# 09_PL_ETH_2.net
KiCad netlist of a schematic drawn in Altium Designer
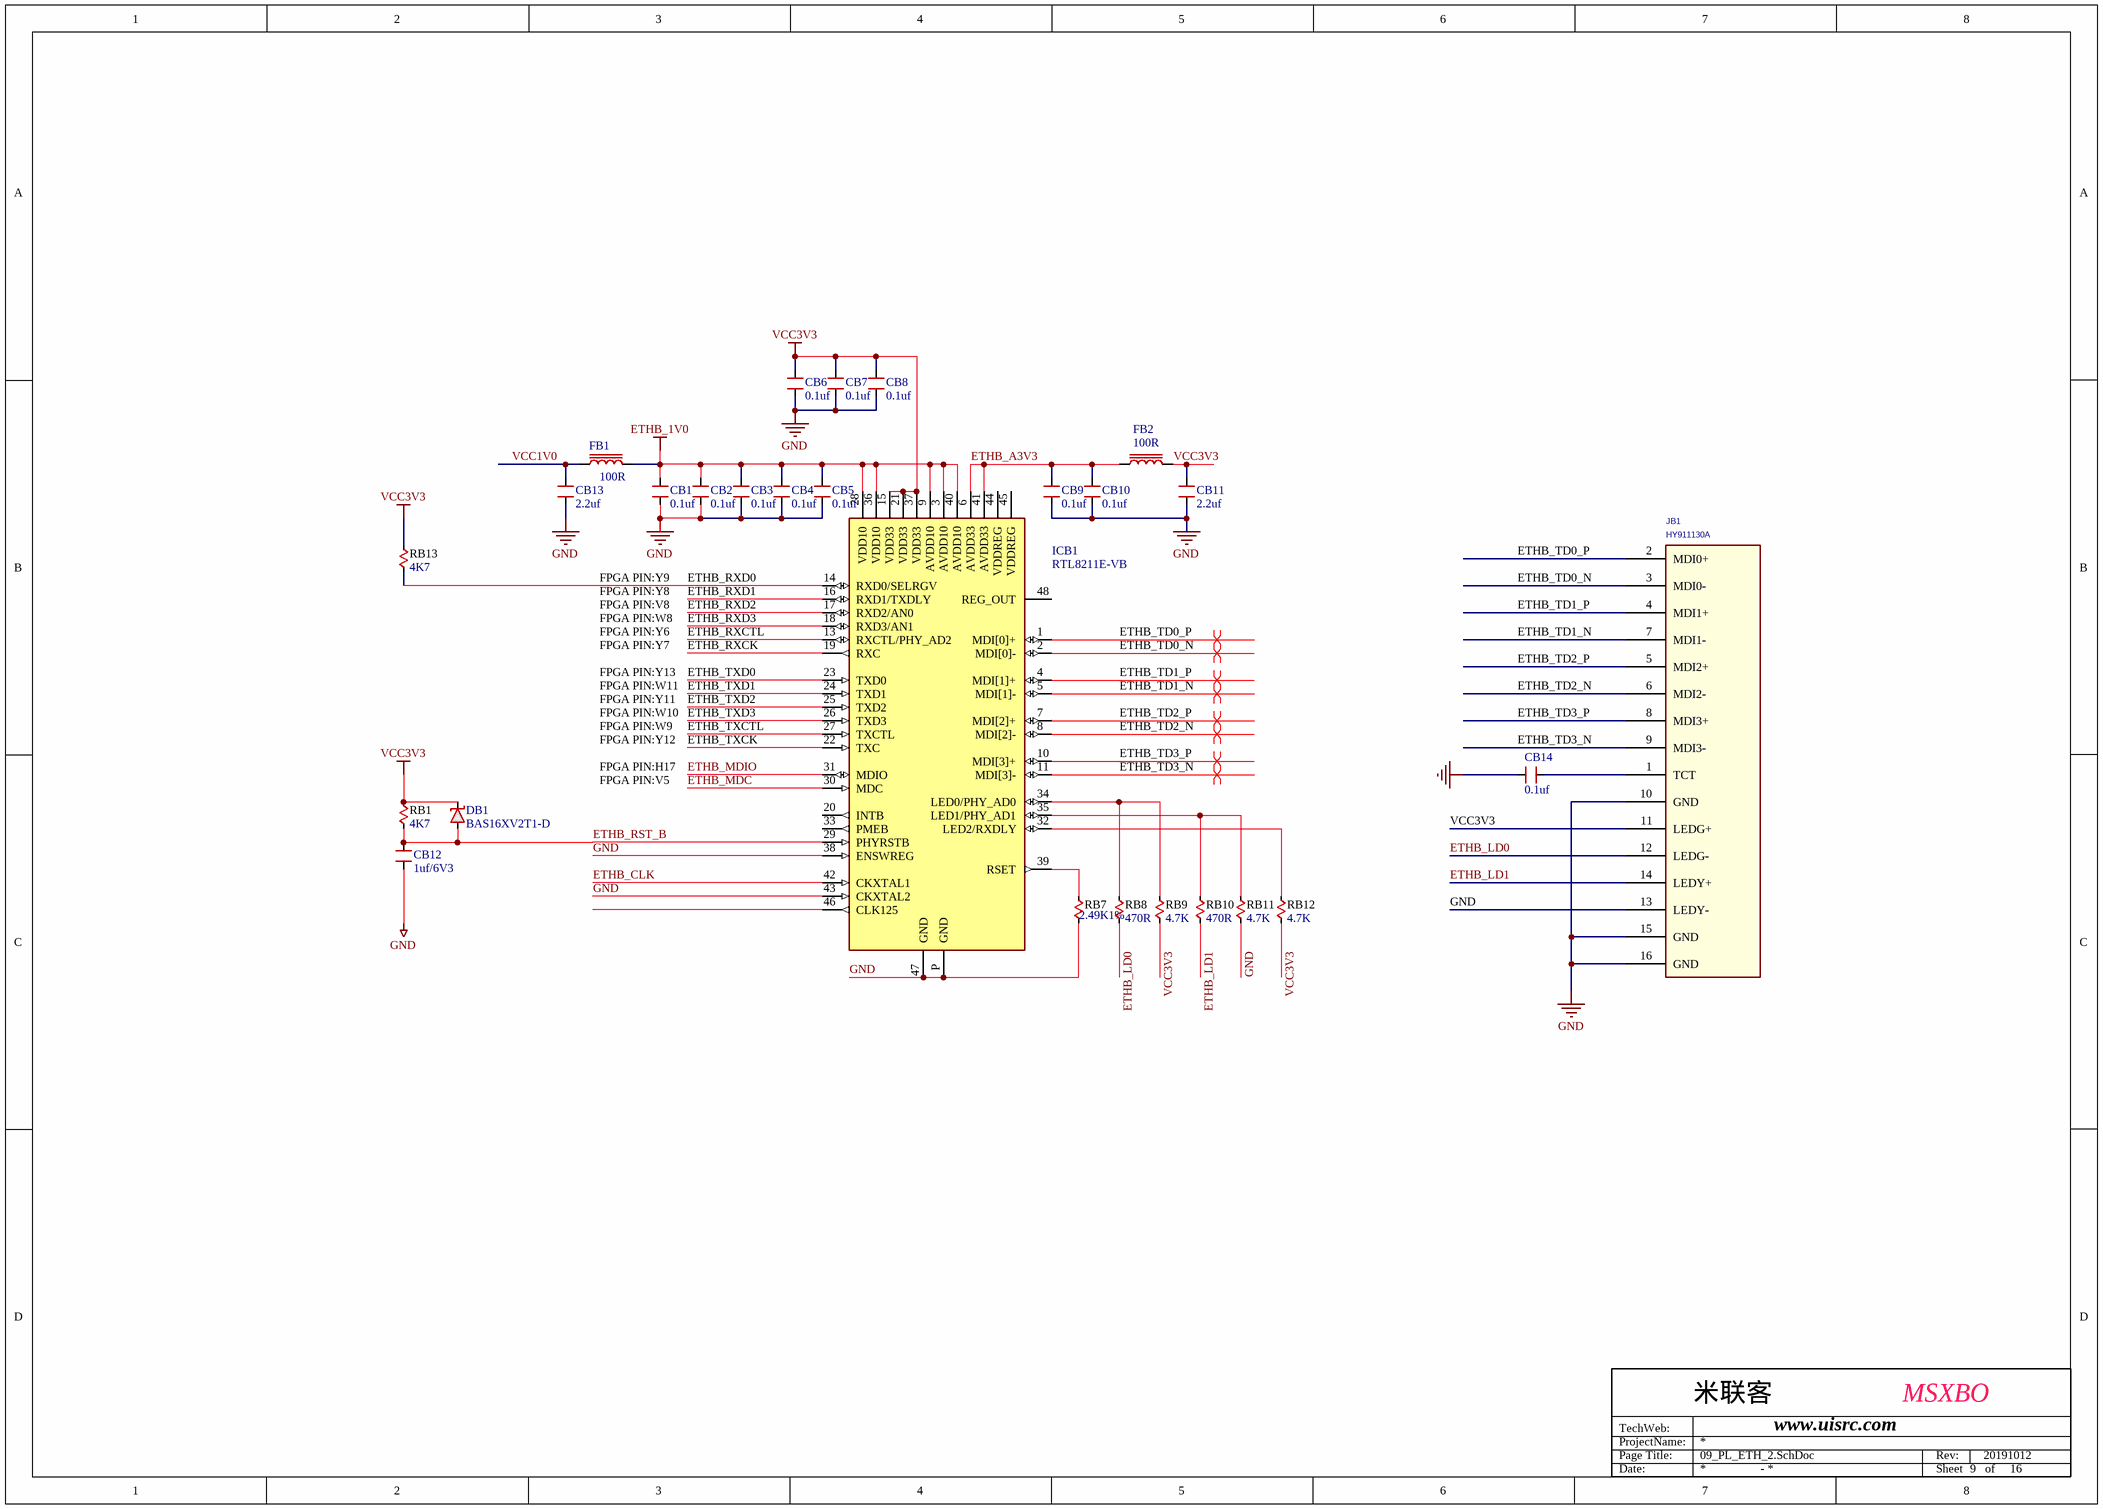
[diagram p0: 09_PL_ETH_2.SchDoc]

(export (version "E")
  (design (tool "Eeschema 10.0.6"))
  (components
    (comp (ref "CB1")
      (value "0.1uf")
      (footprint "CAP0402")
      (description "Generic Capacitor")
      (libsource (lib "Miz701_fun20160215") (part "CAPACITOR"))
    )
    (comp (ref "CB2")
      (value "0.1uf")
      (footprint "CAP0402")
      (description "Generic Capacitor")
      (libsource (lib "Miz701_fun20160215") (part "CAPACITOR"))
    )
    (comp (ref "CB3")
      (value "0.1uf")
      (footprint "CAP0402")
      (description "Generic Capacitor")
      (libsource (lib "Miz701_fun20160215") (part "CAPACITOR"))
    )
    (comp (ref "CB4")
      (value "0.1uf")
      (footprint "CAP0402")
      (description "Generic Capacitor")
      (libsource (lib "Miz701_fun20160215") (part "CAPACITOR"))
    )
    (comp (ref "CB5")
      (value "0.1uf")
      (footprint "CAP0402")
      (description "Generic Capacitor")
      (libsource (lib "Miz701_fun20160215") (part "CAPACITOR"))
    )
    (comp (ref "CB6")
      (value "0.1uf")
      (footprint "CAP0402")
      (description "Generic Capacitor")
      (libsource (lib "Miz701_fun20160215") (part "CAPACITOR"))
    )
    (comp (ref "CB7")
      (value "0.1uf")
      (footprint "CAP0402")
      (description "Generic Capacitor")
      (libsource (lib "Miz701_fun20160215") (part "CAPACITOR"))
    )
    (comp (ref "CB8")
      (value "0.1uf")
      (footprint "CAP0402")
      (description "Generic Capacitor")
      (libsource (lib "Miz701_fun20160215") (part "CAPACITOR"))
    )
    (comp (ref "CB9")
      (value "0.1uf")
      (footprint "CAP0402")
      (description "Generic Capacitor")
      (libsource (lib "Miz701_fun20160215") (part "CAPACITOR"))
    )
    (comp (ref "CB10")
      (value "0.1uf")
      (footprint "CAP0402")
      (description "Generic Capacitor")
      (libsource (lib "Miz701_fun20160215") (part "CAPACITOR"))
    )
    (comp (ref "CB11")
      (value "2.2uf")
      (footprint "CAP0402")
      (description "Generic Capacitor")
      (libsource (lib "Miz701_fun20160215") (part "CAPACITOR"))
    )
    (comp (ref "CB12")
      (value "1uf/6V3")
      (footprint "CAP0402")
      (description "Generic Capacitor")
      (fields (field (name "MANUFACTURER") "Murata"))
      (libsource (lib "Miz702N_fun") (part "CAPACITOR"))
    )
    (comp (ref "CB13")
      (value "2.2uf")
      (footprint "CAP0402")
      (description "Generic Capacitor")
      (libsource (lib "Miz701_fun20160215") (part "CAPACITOR"))
    )
    (comp (ref "CB14")
      (value "0.1uf")
      (footprint "CAP0402")
      (description "Generic Capacitor")
      (libsource (lib "Miz701_fun20160215") (part "CAPACITOR"))
    )
    (comp (ref "DB1")
      (value "BAS16XV2T1-D")
      (footprint "SOD-523")
      (description "Surface Mount ESD Protection Diode")
      (fields (field (name "MANUFACTURER") "On Semiconductor"))
      (libsource (lib "Miz702N_fun") (part "DIODE-SCH"))
    )
    (comp (ref "FB1")
      (value "100R")
      (footprint "CAP0603")
      (description "Generic Ferrite Bead")
      (libsource (lib "Digilent") (part "Ferrite Bead"))
    )
    (comp (ref "FB2")
      (value "100R")
      (footprint "CAP0603")
      (description "Generic Ferrite Bead")
      (libsource (lib "Digilent") (part "Ferrite Bead"))
    )
    (comp (ref "ICB1")
      (value "RTL8211E-VB")
      (footprint "QFN48")
      (libsource (lib "Miz701_fun20160215") (part "RTL8211E-VL"))
    )
    (comp (ref "JB1") (value "HY911130A") (footprint "HY911130A") (libsource (lib "*") (part "HY911130A")))
    (comp (ref "RB1")
      (value "4K7")
      (footprint "RES0402")
      (description "Generic Resistor")
      (libsource (lib "Miz702N_fun") (part "RESISTOR"))
    )
    (comp (ref "RB7")
      (value "2.49K1%")
      (footprint "RES0402")
      (description "Generic Resistor")
      (libsource (lib "Miz701_fun20160215") (part "RESISTOR"))
    )
    (comp (ref "RB8")
      (value "470R")
      (footprint "RES0402")
      (description "Generic Resistor")
      (libsource (lib "Miz701_fun20160215") (part "RESISTOR"))
    )
    (comp (ref "RB9")
      (value "4.7K")
      (footprint "RES0402")
      (description "Generic Resistor")
      (libsource (lib "Miz701_fun20160215") (part "RESISTOR"))
    )
    (comp (ref "RB10")
      (value "470R")
      (footprint "RES0402")
      (description "Generic Resistor")
      (libsource (lib "Miz701_fun20160215") (part "RESISTOR"))
    )
    (comp (ref "RB11")
      (value "4.7K")
      (footprint "RES0402")
      (description "Generic Resistor")
      (libsource (lib "Miz701_fun20160215") (part "RESISTOR"))
    )
    (comp (ref "RB12")
      (value "4.7K")
      (footprint "RES0402")
      (description "Generic Resistor")
      (libsource (lib "Miz701_fun20160215") (part "RESISTOR"))
    )
    (comp (ref "RB13")
      (value "4K7")
      (footprint "RES0402")
      (description "Generic Resistor")
      (libsource (lib "Miz702N_fun") (part "RESISTOR"))
    )
  )
  (nets
    (net (code "1") (name "/ETHB_A3V3") (class "Default")
      (node (ref "CB10") (pin "1") (pinfunction "1_1") (pintype "passive"))
      (node (ref "CB9") (pin "1") (pinfunction "1_1") (pintype "passive"))
      (node (ref "FB2") (pin "1") (pinfunction "1_1") (pintype "passive"))
      (node (ref "ICB1") (pin "41") (pinfunction "AVDD33_41") (pintype "power_in"))
      (node (ref "ICB1") (pin "6") (pinfunction "AVDD33_6") (pintype "power_in"))
    )
    (net (code "2") (name "/ETHB_CLK") (class "Default")
      (node (ref "ICB1") (pin "42") (pinfunction "CKXTAL1_42") (pintype "input"))
    )
    (net (code "3") (name "/ETHB_LD0") (class "Default")
      (node (ref "JB1") (pin "12") (pinfunction "LEDG-_12") (pintype "passive"))
      (node (ref "RB8") (pin "2") (pinfunction "2_2") (pintype "passive"))
    )
    (net (code "4") (name "/ETHB_LD1") (class "Default")
      (node (ref "JB1") (pin "14") (pinfunction "LEDY+_14") (pintype "passive"))
      (node (ref "RB10") (pin "2") (pinfunction "2_2") (pintype "passive"))
    )
    (net (code "5") (name "/ETHB_MDC") (class "Default")
      (node (ref "ICB1") (pin "30") (pinfunction "MDC_30") (pintype "input"))
    )
    (net (code "6") (name "/ETHB_MDIO") (class "Default")
      (node (ref "ICB1") (pin "31") (pinfunction "MDIO_31") (pintype "bidirectional"))
    )
    (net (code "7") (name "/ETHB_RST_B") (class "Default")
      (node (ref "CB12") (pin "1") (pinfunction "1_1") (pintype "passive"))
      (node (ref "DB1") (pin "A") (pinfunction "A_A") (pintype "passive"))
      (node (ref "ICB1") (pin "29") (pinfunction "PHYRSTB_29") (pintype "input"))
      (node (ref "RB1") (pin "2") (pinfunction "2_2") (pintype "passive"))
    )
    (net (code "8") (name "/ETHB_RXCK") (class "Default")
      (node (ref "ICB1") (pin "19") (pinfunction "RXC_19") (pintype "output"))
    )
    (net (code "9") (name "/ETHB_RXCTL") (class "Default")
      (node (ref "ICB1") (pin "13") (pinfunction "RXCTL/PHY_AD2_13") (pintype "bidirectional"))
    )
    (net (code "10") (name "/ETHB_RXD0") (class "Default")
      (node (ref "ICB1") (pin "14") (pinfunction "RXD0/SELRGV_14") (pintype "bidirectional"))
      (node (ref "RB13") (pin "2") (pinfunction "2_2") (pintype "passive"))
    )
    (net (code "11") (name "/ETHB_RXD1") (class "Default")
      (node (ref "ICB1") (pin "16") (pinfunction "RXD1/TXDLY_16") (pintype "bidirectional"))
    )
    (net (code "12") (name "/ETHB_RXD2") (class "Default")
      (node (ref "ICB1") (pin "17") (pinfunction "RXD2/AN0_17") (pintype "bidirectional"))
    )
    (net (code "13") (name "/ETHB_RXD3") (class "Default")
      (node (ref "ICB1") (pin "18") (pinfunction "RXD3/AN1_18") (pintype "bidirectional"))
    )
    (net (code "14") (name "/ETHB_TD0_N") (class "Default")
      (node (ref "ICB1") (pin "2") (pinfunction "MDI[0]-_2") (pintype "bidirectional"))
      (node (ref "JB1") (pin "3") (pinfunction "MDI0-_3") (pintype "passive"))
    )
    (net (code "15") (name "/ETHB_TD0_P") (class "Default")
      (node (ref "ICB1") (pin "1") (pinfunction "MDI[0]+_1") (pintype "bidirectional"))
      (node (ref "JB1") (pin "2") (pinfunction "MDI0+_2") (pintype "passive"))
    )
    (net (code "16") (name "/ETHB_TD1_N") (class "Default")
      (node (ref "ICB1") (pin "5") (pinfunction "MDI[1]-_5") (pintype "bidirectional"))
      (node (ref "JB1") (pin "7") (pinfunction "MDI1-_7") (pintype "passive"))
    )
    (net (code "17") (name "/ETHB_TD1_P") (class "Default")
      (node (ref "ICB1") (pin "4") (pinfunction "MDI[1]+_4") (pintype "bidirectional"))
      (node (ref "JB1") (pin "4") (pinfunction "MDI1+_4") (pintype "passive"))
    )
    (net (code "18") (name "/ETHB_TD2_N") (class "Default")
      (node (ref "ICB1") (pin "8") (pinfunction "MDI[2]-_8") (pintype "bidirectional"))
      (node (ref "JB1") (pin "6") (pinfunction "MDI2-_6") (pintype "passive"))
    )
    (net (code "19") (name "/ETHB_TD2_P") (class "Default")
      (node (ref "ICB1") (pin "7") (pinfunction "MDI[2]+_7") (pintype "bidirectional"))
      (node (ref "JB1") (pin "5") (pinfunction "MDI2+_5") (pintype "passive"))
    )
    (net (code "20") (name "/ETHB_TD3_N") (class "Default")
      (node (ref "ICB1") (pin "11") (pinfunction "MDI[3]-_11") (pintype "bidirectional"))
      (node (ref "JB1") (pin "9") (pinfunction "MDI3-_9") (pintype "passive"))
    )
    (net (code "21") (name "/ETHB_TD3_P") (class "Default")
      (node (ref "ICB1") (pin "10") (pinfunction "MDI[3]+_10") (pintype "bidirectional"))
      (node (ref "JB1") (pin "8") (pinfunction "MDI3+_8") (pintype "passive"))
    )
    (net (code "22") (name "/ETHB_TXCK") (class "Default")
      (node (ref "ICB1") (pin "22") (pinfunction "TXC_22") (pintype "input"))
    )
    (net (code "23") (name "/ETHB_TXCTL") (class "Default")
      (node (ref "ICB1") (pin "27") (pinfunction "TXCTL_27") (pintype "input"))
    )
    (net (code "24") (name "/ETHB_TXD0") (class "Default")
      (node (ref "ICB1") (pin "23") (pinfunction "TXD0_23") (pintype "input"))
    )
    (net (code "25") (name "/ETHB_TXD1") (class "Default")
      (node (ref "ICB1") (pin "24") (pinfunction "TXD1_24") (pintype "input"))
    )
    (net (code "26") (name "/ETHB_TXD2") (class "Default")
      (node (ref "ICB1") (pin "25") (pinfunction "TXD2_25") (pintype "input"))
    )
    (net (code "27") (name "/ETHB_TXD3") (class "Default")
      (node (ref "ICB1") (pin "26") (pinfunction "TXD3_26") (pintype "input"))
    )
    (net (code "28") (name "/VCC1V0") (class "Default")
      (node (ref "CB13") (pin "1") (pinfunction "1_1") (pintype "passive"))
      (node (ref "FB1") (pin "1") (pinfunction "1_1") (pintype "passive"))
    )
    (net (code "29") (name "ETHB_1V0") (class "Default")
      (node (ref "CB1") (pin "1") (pinfunction "1_1") (pintype "passive"))
      (node (ref "CB2") (pin "1") (pinfunction "1_1") (pintype "passive"))
      (node (ref "CB3") (pin "1") (pinfunction "1_1") (pintype "passive"))
      (node (ref "CB4") (pin "1") (pinfunction "1_1") (pintype "passive"))
      (node (ref "CB5") (pin "1") (pinfunction "1_1") (pintype "passive"))
      (node (ref "FB1") (pin "2") (pinfunction "2_2") (pintype "passive"))
      (node (ref "ICB1") (pin "28") (pinfunction "VDD10_28") (pintype "power_in"))
      (node (ref "ICB1") (pin "3") (pinfunction "AVDD10_3") (pintype "power_in"))
      (node (ref "ICB1") (pin "36") (pinfunction "VDD10_36") (pintype "power_in"))
      (node (ref "ICB1") (pin "40") (pinfunction "AVDD10_40") (pintype "power_in"))
      (node (ref "ICB1") (pin "9") (pinfunction "AVDD10_9") (pintype "power_in"))
    )
    (net (code "30") (name "GND") (class "Default")
      (node (ref "CB1") (pin "2") (pinfunction "2_2") (pintype "passive"))
      (node (ref "CB10") (pin "2") (pinfunction "2_2") (pintype "passive"))
      (node (ref "CB11") (pin "2") (pinfunction "2_2") (pintype "passive"))
      (node (ref "CB12") (pin "2") (pinfunction "2_2") (pintype "passive"))
      (node (ref "CB13") (pin "2") (pinfunction "2_2") (pintype "passive"))
      (node (ref "CB14") (pin "1") (pinfunction "1_1") (pintype "passive"))
      (node (ref "CB2") (pin "2") (pinfunction "2_2") (pintype "passive"))
      (node (ref "CB3") (pin "2") (pinfunction "2_2") (pintype "passive"))
      (node (ref "CB4") (pin "2") (pinfunction "2_2") (pintype "passive"))
      (node (ref "CB5") (pin "2") (pinfunction "2_2") (pintype "passive"))
      (node (ref "CB6") (pin "2") (pinfunction "2_2") (pintype "passive"))
      (node (ref "CB7") (pin "2") (pinfunction "2_2") (pintype "passive"))
      (node (ref "CB8") (pin "2") (pinfunction "2_2") (pintype "passive"))
      (node (ref "CB9") (pin "2") (pinfunction "2_2") (pintype "passive"))
      (node (ref "ICB1") (pin "38") (pinfunction "ENSWREG_38") (pintype "input"))
      (node (ref "ICB1") (pin "43") (pinfunction "CKXTAL2_43") (pintype "input"))
      (node (ref "ICB1") (pin "47") (pinfunction "GND_47") (pintype "power_in"))
      (node (ref "ICB1") (pin "P") (pinfunction "GND_P") (pintype "power_in"))
      (node (ref "JB1") (pin "10") (pinfunction "GND_10") (pintype "power_in"))
      (node (ref "JB1") (pin "13") (pinfunction "LEDY-_13") (pintype "passive"))
      (node (ref "JB1") (pin "15") (pinfunction "GND_15") (pintype "power_in"))
      (node (ref "JB1") (pin "16") (pinfunction "GND_16") (pintype "power_in"))
      (node (ref "RB11") (pin "2") (pinfunction "2_2") (pintype "passive"))
      (node (ref "RB7") (pin "2") (pinfunction "2_2") (pintype "passive"))
    )
    (net (code "31") (name "Net-(ICB1-LED0{slash}PHY_AD0)") (class "Default")
      (node (ref "ICB1") (pin "34") (pinfunction "LED0/PHY_AD0_34") (pintype "bidirectional"))
      (node (ref "RB8") (pin "1") (pinfunction "1_1") (pintype "passive"))
      (node (ref "RB9") (pin "1") (pinfunction "1_1") (pintype "passive"))
    )
    (net (code "32") (name "Net-(ICB1-LED1{slash}PHY_AD1)") (class "Default")
      (node (ref "ICB1") (pin "35") (pinfunction "LED1/PHY_AD1_35") (pintype "bidirectional"))
      (node (ref "RB10") (pin "1") (pinfunction "1_1") (pintype "passive"))
      (node (ref "RB11") (pin "1") (pinfunction "1_1") (pintype "passive"))
    )
    (net (code "33") (name "Net-(ICB1-LED2{slash}RXDLY)") (class "Default")
      (node (ref "ICB1") (pin "32") (pinfunction "LED2/RXDLY_32") (pintype "bidirectional"))
      (node (ref "RB12") (pin "1") (pinfunction "1_1") (pintype "passive"))
    )
    (net (code "34") (name "Net-(ICB1-RSET)") (class "Default")
      (node (ref "ICB1") (pin "39") (pinfunction "RSET_39") (pintype "output"))
      (node (ref "RB7") (pin "1") (pinfunction "1_1") (pintype "passive"))
    )
    (net (code "35") (name "Net-(JB1-TCT)") (class "Default")
      (node (ref "CB14") (pin "2") (pinfunction "2_2") (pintype "passive"))
      (node (ref "JB1") (pin "1") (pinfunction "TCT_1") (pintype "passive"))
    )
    (net (code "36") (name "VCC3V3") (class "Default")
      (node (ref "CB11") (pin "1") (pinfunction "1_1") (pintype "passive"))
      (node (ref "CB6") (pin "1") (pinfunction "1_1") (pintype "passive"))
      (node (ref "CB7") (pin "1") (pinfunction "1_1") (pintype "passive"))
      (node (ref "CB8") (pin "1") (pinfunction "1_1") (pintype "passive"))
      (node (ref "DB1") (pin "K") (pinfunction "K_K") (pintype "passive"))
      (node (ref "FB2") (pin "2") (pinfunction "2_2") (pintype "passive"))
      (node (ref "ICB1") (pin "15") (pinfunction "VDD33_15") (pintype "power_in"))
      (node (ref "ICB1") (pin "21") (pinfunction "VDD33_21") (pintype "power_in"))
      (node (ref "ICB1") (pin "37") (pinfunction "VDD33_37") (pintype "power_in"))
      (node (ref "JB1") (pin "11") (pinfunction "LEDG+_11") (pintype "passive"))
      (node (ref "RB1") (pin "1") (pinfunction "1_1") (pintype "passive"))
      (node (ref "RB12") (pin "2") (pinfunction "2_2") (pintype "passive"))
      (node (ref "RB13") (pin "1") (pinfunction "1_1") (pintype "passive"))
      (node (ref "RB9") (pin "2") (pinfunction "2_2") (pintype "passive"))
    )
    (net (code "37") (name "unconnected-(ICB1-CLK125-Pad46)") (class "Default")
      (node (ref "ICB1") (pin "46") (pinfunction "CLK125_46") (pintype "output"))
    )
    (net (code "38") (name "unconnected-(ICB1-INTB-Pad20)") (class "Default")
      (node (ref "ICB1") (pin "20") (pinfunction "INTB_20") (pintype "output"))
    )
    (net (code "39") (name "unconnected-(ICB1-PMEB-Pad33)") (class "Default")
      (node (ref "ICB1") (pin "33") (pinfunction "PMEB_33") (pintype "output"))
    )
    (net (code "40") (name "unconnected-(ICB1-REG_OUT-Pad48)") (class "Default")
      (node (ref "ICB1") (pin "48") (pinfunction "REG_OUT_48") (pintype "power_in"))
    )
    (net (code "41") (name "unconnected-(ICB1-VDDREG-Pad44)") (class "Default")
      (node (ref "ICB1") (pin "44") (pinfunction "VDDREG_44") (pintype "power_in"))
    )
    (net (code "42") (name "unconnected-(ICB1-VDDREG-Pad45)") (class "Default")
      (node (ref "ICB1") (pin "45") (pinfunction "VDDREG_45") (pintype "power_in"))
    )
  )
)
